# Driver_LCD.net
KiCad netlist of a schematic drawn in Altium Designer
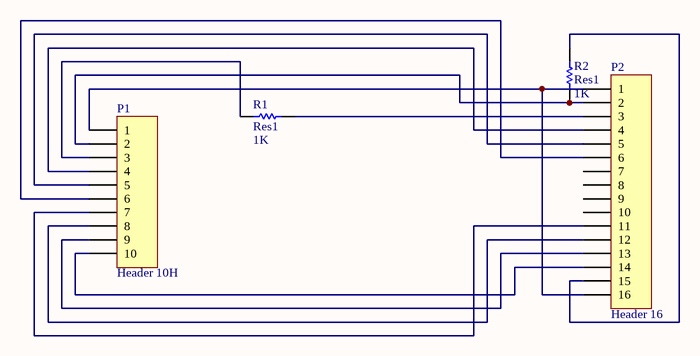
[diagram p0: Driver LCD.SchDoc]

(export (version "E")
  (design (tool "Eeschema 10.0.6"))
  (components
    (comp (ref "P1")
      (value "Header 10H")
      (footprint "HDR1X10H")
      (description "Header, 10-Pin, Right Angle")
      (fields (field (name "PUBLISHER") "Altium Limited"))
      (libsource (lib "Miscellaneous Connectors") (part "Header 10H"))
    )
    (comp (ref "P2")
      (value "Header 16")
      (footprint "HDR1X16")
      (description "Header, 16-Pin")
      (fields (field (name "PUBLISHER") "Altium Limited"))
      (libsource (lib "Miscellaneous Connectors") (part "Header 16"))
    )
    (comp (ref "R1")
      (value "Res1")
      (footprint "AXIAL-0.3")
      (description "Resistor")
      (fields (field (name "ALTIUM_VALUE") "1K") (field (name "PUBLISHER") "Altium Limited"))
      (libsource (lib "Miscellaneous Devices") (part "Res1"))
    )
    (comp (ref "R2")
      (value "Res1")
      (footprint "AXIAL-0.3")
      (description "Resistor")
      (fields (field (name "ALTIUM_VALUE") "1K") (field (name "PUBLISHER") "Altium Limited"))
      (libsource (lib "Miscellaneous Devices") (part "Res1"))
    )
  )
  (nets
    (net (code "1") (name "Net-(P1-Pad1)") (class "Default")
      (node (ref "P1") (pin "1") (pinfunction "1_1") (pintype "passive"))
      (node (ref "P2") (pin "1") (pinfunction "1_1") (pintype "passive"))
      (node (ref "P2") (pin "16") (pinfunction "16_16") (pintype "passive"))
    )
    (net (code "2") (name "Net-(P1-Pad2)") (class "Default")
      (node (ref "P1") (pin "2") (pinfunction "2_2") (pintype "passive"))
      (node (ref "P2") (pin "2") (pinfunction "2_2") (pintype "passive"))
      (node (ref "R2") (pin "1") (pinfunction "1_1") (pintype "passive"))
    )
    (net (code "3") (name "Net-(P1-Pad3)") (class "Default")
      (node (ref "P1") (pin "3") (pinfunction "3_3") (pintype "passive"))
      (node (ref "R1") (pin "1") (pinfunction "1_1") (pintype "passive"))
    )
    (net (code "4") (name "Net-(P1-Pad4)") (class "Default")
      (node (ref "P1") (pin "4") (pinfunction "4_4") (pintype "passive"))
      (node (ref "P2") (pin "4") (pinfunction "4_4") (pintype "passive"))
    )
    (net (code "5") (name "Net-(P1-Pad5)") (class "Default")
      (node (ref "P1") (pin "5") (pinfunction "5_5") (pintype "passive"))
      (node (ref "P2") (pin "5") (pinfunction "5_5") (pintype "passive"))
    )
    (net (code "6") (name "Net-(P1-Pad6)") (class "Default")
      (node (ref "P1") (pin "6") (pinfunction "6_6") (pintype "passive"))
      (node (ref "P2") (pin "6") (pinfunction "6_6") (pintype "passive"))
    )
    (net (code "7") (name "Net-(P1-Pad7)") (class "Default")
      (node (ref "P1") (pin "7") (pinfunction "7_7") (pintype "passive"))
      (node (ref "P2") (pin "11") (pinfunction "11_11") (pintype "passive"))
    )
    (net (code "8") (name "Net-(P1-Pad8)") (class "Default")
      (node (ref "P1") (pin "8") (pinfunction "8_8") (pintype "passive"))
      (node (ref "P2") (pin "12") (pinfunction "12_12") (pintype "passive"))
    )
    (net (code "9") (name "Net-(P1-Pad9)") (class "Default")
      (node (ref "P1") (pin "9") (pinfunction "9_9") (pintype "passive"))
      (node (ref "P2") (pin "13") (pinfunction "13_13") (pintype "passive"))
    )
    (net (code "10") (name "Net-(P1-Pad10)") (class "Default")
      (node (ref "P1") (pin "10") (pinfunction "10_10") (pintype "passive"))
      (node (ref "P2") (pin "14") (pinfunction "14_14") (pintype "passive"))
    )
    (net (code "11") (name "Net-(P2-Pad3)") (class "Default")
      (node (ref "P2") (pin "3") (pinfunction "3_3") (pintype "passive"))
      (node (ref "R1") (pin "2") (pinfunction "2_2") (pintype "passive"))
    )
    (net (code "12") (name "Net-(P2-Pad15)") (class "Default")
      (node (ref "P2") (pin "15") (pinfunction "15_15") (pintype "passive"))
      (node (ref "R2") (pin "2") (pinfunction "2_2") (pintype "passive"))
    )
    (net (code "13") (name "unconnected-(P2-Pad7)") (class "Default")
      (node (ref "P2") (pin "7") (pinfunction "7_7") (pintype "passive"))
    )
    (net (code "14") (name "unconnected-(P2-Pad8)") (class "Default")
      (node (ref "P2") (pin "8") (pinfunction "8_8") (pintype "passive"))
    )
    (net (code "15") (name "unconnected-(P2-Pad9)") (class "Default")
      (node (ref "P2") (pin "9") (pinfunction "9_9") (pintype "passive"))
    )
    (net (code "16") (name "unconnected-(P2-Pad10)") (class "Default")
      (node (ref "P2") (pin "10") (pinfunction "10_10") (pintype "passive"))
    )
  )
)
